# rega.net
KiCad netlist of a schematic drawn in EAGLE
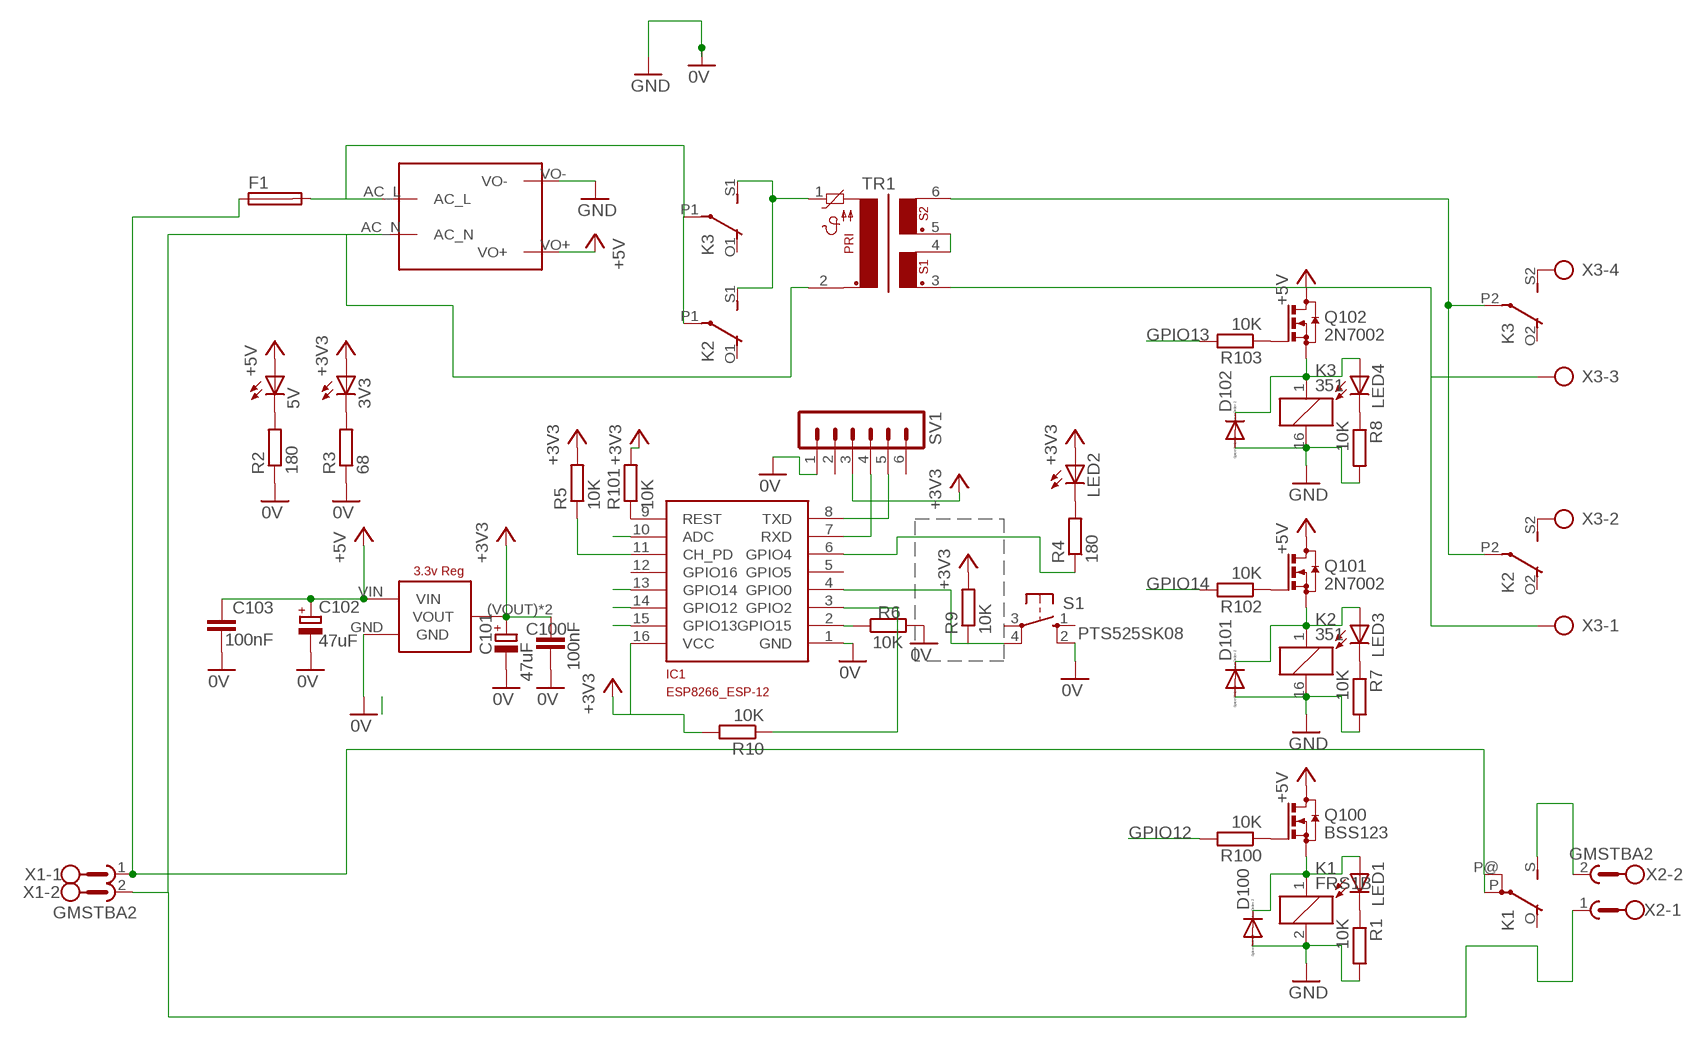
[diagram p0: schematic, sheet 1]

(export (version "E")
  (design (tool "Eeschema 10.0.6"))
  (components
    (comp (ref "3V3")
      (value "LEDCHIPLED_0805")
      (footprint "eagle-import:CHIPLED_0805")
      (libsource (lib "eagle-import") (part "LEDCHIPLED_0805"))
    )
    (comp (ref "5V")
      (value "LEDCHIPLED_0805")
      (footprint "eagle-import:CHIPLED_0805")
      (libsource (lib "eagle-import") (part "LEDCHIPLED_0805"))
    )
    (comp (ref "C100")
      (value "100nF")
      (footprint "eagle-import:C0805")
      (libsource (lib "eagle-import") (part "C-EUC0805"))
    )
    (comp (ref "C101")
      (value "47uF")
      (footprint "eagle-import:CT3528")
      (libsource (lib "eagle-import") (part "CPOL-EUCT3528"))
    )
    (comp (ref "C102")
      (value "47uF")
      (footprint "eagle-import:CT3528")
      (libsource (lib "eagle-import") (part "CPOL-EUCT3528"))
    )
    (comp (ref "C103")
      (value "100nF")
      (footprint "eagle-import:C0805")
      (libsource (lib "eagle-import") (part "C-EUC0805"))
    )
    (comp (ref "D100")
      (value "DIODE-SOD80C")
      (footprint "eagle-import:SOD80C")
      (libsource (lib "eagle-import") (part "DIODE-SOD80C"))
    )
    (comp (ref "D101")
      (value "DIODE-SOD80C")
      (footprint "eagle-import:SOD80C")
      (libsource (lib "eagle-import") (part "DIODE-SOD80C"))
    )
    (comp (ref "D102")
      (value "DIODE-SOD80C")
      (footprint "eagle-import:SOD80C")
      (libsource (lib "eagle-import") (part "DIODE-SOD80C"))
    )
    (comp (ref "F1")
      (value "LITTLEFUSESMD")
      (footprint "eagle-import:SMD")
      (libsource (lib "eagle-import") (part "LITTLEFUSESMD"))
    )
    (comp (ref "IC1")
      (value "ESP8266_ESP-12")
      (footprint "eagle-import:ESP8266-ESP12")
      (libsource (lib "eagle-import") (part "ESP8266_ESP-12"))
    )
    (comp (ref "K1")
      (value "FRS1B")
      (footprint "eagle-import:FRS1B")
      (libsource (lib "eagle-import") (part "FRS1B"))
    )
    (comp (ref "K2")
      (value "351")
      (footprint "eagle-import:351")
      (libsource (lib "eagle-import") (part "351"))
    )
    (comp (ref "K3")
      (value "351")
      (footprint "eagle-import:351")
      (libsource (lib "eagle-import") (part "351"))
    )
    (comp (ref "LED1")
      (value "LEDSML0805")
      (footprint "eagle-import:SML0805")
      (libsource (lib "eagle-import") (part "LEDSML0805"))
    )
    (comp (ref "LED2")
      (value "LEDCHIPLED_0805")
      (footprint "eagle-import:CHIPLED_0805")
      (libsource (lib "eagle-import") (part "LEDCHIPLED_0805"))
    )
    (comp (ref "LED3")
      (value "LEDSML0805")
      (footprint "eagle-import:SML0805")
      (libsource (lib "eagle-import") (part "LEDSML0805"))
    )
    (comp (ref "LED4")
      (value "LEDSML0805")
      (footprint "eagle-import:SML0805")
      (libsource (lib "eagle-import") (part "LEDSML0805"))
    )
    (comp (ref "Q100")
      (value "BSS123")
      (footprint "eagle-import:SOT23")
      (libsource (lib "eagle-import") (part "BSS123"))
    )
    (comp (ref "Q101")
      (value "2N7002")
      (footprint "eagle-import:SOT23")
      (libsource (lib "eagle-import") (part "BSS123"))
    )
    (comp (ref "Q102")
      (value "2N7002")
      (footprint "eagle-import:SOT23")
      (libsource (lib "eagle-import") (part "BSS123"))
    )
    (comp (ref "R1")
      (value "10K")
      (footprint "eagle-import:R0805")
      (libsource (lib "eagle-import") (part "resistor_R-EU_R0805"))
    )
    (comp (ref "R2")
      (value "180")
      (footprint "eagle-import:R0805")
      (libsource (lib "eagle-import") (part "R-EU_R0805"))
    )
    (comp (ref "R3")
      (value "68")
      (footprint "eagle-import:R0805")
      (libsource (lib "eagle-import") (part "R-EU_R0805"))
    )
    (comp (ref "R4")
      (value "180")
      (footprint "eagle-import:R0805")
      (libsource (lib "eagle-import") (part "R-EU_R0805"))
    )
    (comp (ref "R5")
      (value "10K")
      (footprint "eagle-import:R0805")
      (libsource (lib "eagle-import") (part "R-EU_R0805"))
    )
    (comp (ref "R6")
      (value "10K")
      (footprint "eagle-import:R0805")
      (libsource (lib "eagle-import") (part "R-EU_R0805"))
    )
    (comp (ref "R7")
      (value "10K")
      (footprint "eagle-import:R0805")
      (libsource (lib "eagle-import") (part "resistor_R-EU_R0805"))
    )
    (comp (ref "R8")
      (value "10K")
      (footprint "eagle-import:R0805")
      (libsource (lib "eagle-import") (part "resistor_R-EU_R0805"))
    )
    (comp (ref "R9")
      (value "10K")
      (footprint "eagle-import:R0805")
      (libsource (lib "eagle-import") (part "R-EU_R0805"))
    )
    (comp (ref "R10")
      (value "10K")
      (footprint "eagle-import:R0805")
      (libsource (lib "eagle-import") (part "R-EU_R0805"))
    )
    (comp (ref "R100")
      (value "10K")
      (footprint "eagle-import:R0805")
      (libsource (lib "eagle-import") (part "resistor_R-EU_R0805"))
    )
    (comp (ref "R101")
      (value "10K")
      (footprint "eagle-import:R0805")
      (libsource (lib "eagle-import") (part "R-EU_R0805"))
    )
    (comp (ref "R102")
      (value "10K")
      (footprint "eagle-import:R0805")
      (libsource (lib "eagle-import") (part "resistor_R-EU_R0805"))
    )
    (comp (ref "R103")
      (value "10K")
      (footprint "eagle-import:R0805")
      (libsource (lib "eagle-import") (part "resistor_R-EU_R0805"))
    )
    (comp (ref "S1")
      (value "PTS525SK08")
      (footprint "eagle-import:SM08")
      (fields (field (name "MF") "C&K Components") (field (name "MPN") "PTS525SK08SMTR2LFS"))
      (libsource (lib "eagle-import") (part "PTS52508SK"))
    )
    (comp (ref "SV1")
      (value "MA06-1")
      (footprint "eagle-import:MA06-1")
      (libsource (lib "eagle-import") (part "MA06-1"))
    )
    (comp (ref "TR1")
      (value "PT13-2")
      (footprint "eagle-import:PT13-2")
      (libsource (lib "eagle-import") (part "PT13-2"))
    )
    (comp (ref "U$1")
      (value "MAINS_CONVERTERS")
      (footprint "eagle-import:HLK-PM01")
      (libsource (lib "eagle-import") (part "MAINS_CONVERTERS"))
    )
    (comp (ref "U$100")
      (value "LD1117")
      (footprint "eagle-import:LD1117SOT-223")
      (libsource (lib "eagle-import") (part "LD1117"))
    )
    (comp (ref "X1")
      (value "GMSTBA2")
      (footprint "eagle-import:GMSTBA2")
      (fields (field (name "MF") "FARNELL") (field (name "MPN") "1757242"))
      (libsource (lib "eagle-import") (part "GMSTBA2"))
    )
    (comp (ref "X2")
      (value "GMSTBA2")
      (footprint "eagle-import:GMSTBA2")
      (fields (field (name "MF") "FARNELL") (field (name "MPN") "1757242"))
      (libsource (lib "eagle-import") (part "GMSTBA2"))
    )
    (comp (ref "X3")
      (value "AK300/4")
      (footprint "eagle-import:AK300_4")
      (libsource (lib "eagle-import") (part "AK300/4"))
    )
  )
  (nets
    (net (code "1") (name "+3V3") (class "Default")
      (node (ref "3V3") (pin "A") (pinfunction "A_A") (pintype "passive"))
      (node (ref "C100") (pin "1") (pinfunction "1_1") (pintype "passive"))
      (node (ref "C101") (pin "+") (pinfunction "+_+") (pintype "passive"))
      (node (ref "IC1") (pin "16") (pinfunction "VCC_16") (pintype "bidirectional"))
      (node (ref "LED2") (pin "A") (pinfunction "A_A") (pintype "passive"))
      (node (ref "R10") (pin "2") (pinfunction "2_2") (pintype "passive"))
      (node (ref "R101") (pin "2") (pinfunction "2_2") (pintype "passive"))
      (node (ref "R5") (pin "2") (pinfunction "2_2") (pintype "passive"))
      (node (ref "R9") (pin "2") (pinfunction "2_2") (pintype "passive"))
      (node (ref "SV1") (pin "3") (pinfunction "3_3") (pintype "passive"))
      (node (ref "U$100") (pin "(VOUT)") (pinfunction "VOUT_(VOUT)") (pintype "bidirectional"))
      (node (ref "U$100") (pin "VOUT") (pinfunction "VOUT_VOUT") (pintype "bidirectional"))
    )
    (net (code "2") (name "+5V") (class "Default")
      (node (ref "5V") (pin "A") (pinfunction "A_A") (pintype "passive"))
      (node (ref "C102") (pin "+") (pinfunction "+_+") (pintype "passive"))
      (node (ref "C103") (pin "1") (pinfunction "1_1") (pintype "passive"))
      (node (ref "Q100") (pin "3") (pinfunction "D_3") (pintype "passive"))
      (node (ref "Q101") (pin "3") (pinfunction "D_3") (pintype "passive"))
      (node (ref "Q102") (pin "3") (pinfunction "D_3") (pintype "passive"))
      (node (ref "U$1") (pin "VO+") (pinfunction "VO+_VO+") (pintype "output"))
      (node (ref "U$100") (pin "VIN") (pinfunction "VIN_VIN") (pintype "bidirectional"))
    )
    (net (code "3") (name "/GPIO12") (class "Default")
      (node (ref "IC1") (pin "14") (pinfunction "GPIO12_14") (pintype "bidirectional"))
      (node (ref "R100") (pin "2") (pinfunction "2_2") (pintype "passive"))
    )
    (net (code "4") (name "/GPIO13") (class "Default")
      (node (ref "IC1") (pin "15") (pinfunction "GPIO13_15") (pintype "bidirectional"))
      (node (ref "R103") (pin "2") (pinfunction "2_2") (pintype "passive"))
    )
    (net (code "5") (name "/GPIO14") (class "Default")
      (node (ref "IC1") (pin "13") (pinfunction "GPIO14_13") (pintype "bidirectional"))
      (node (ref "R102") (pin "2") (pinfunction "2_2") (pintype "passive"))
    )
    (net (code "6") (name "0V") (class "Default")
      (node (ref "C100") (pin "2") (pinfunction "2_2") (pintype "passive"))
      (node (ref "C101") (pin "-") (pinfunction "-_-") (pintype "passive"))
      (node (ref "C102") (pin "-") (pinfunction "-_-") (pintype "passive"))
      (node (ref "C103") (pin "2") (pinfunction "2_2") (pintype "passive"))
      (node (ref "D100") (pin "A") (pinfunction "A_A") (pintype "passive"))
      (node (ref "D101") (pin "A") (pinfunction "A_A") (pintype "passive"))
      (node (ref "D102") (pin "A") (pinfunction "A_A") (pintype "passive"))
      (node (ref "IC1") (pin "1") (pinfunction "GND_1") (pintype "bidirectional"))
      (node (ref "K1") (pin "2") (pinfunction "2_2") (pintype "passive"))
      (node (ref "K2") (pin "16") (pinfunction "2_16") (pintype "passive"))
      (node (ref "K3") (pin "16") (pinfunction "2_16") (pintype "passive"))
      (node (ref "R1") (pin "2") (pinfunction "2_2") (pintype "passive"))
      (node (ref "R2") (pin "1") (pinfunction "1_1") (pintype "passive"))
      (node (ref "R3") (pin "1") (pinfunction "1_1") (pintype "passive"))
      (node (ref "R6") (pin "2") (pinfunction "2_2") (pintype "passive"))
      (node (ref "R7") (pin "2") (pinfunction "2_2") (pintype "passive"))
      (node (ref "R8") (pin "2") (pinfunction "2_2") (pintype "passive"))
      (node (ref "S1") (pin "2") (pinfunction "S_2") (pintype "passive"))
      (node (ref "SV1") (pin "1") (pinfunction "1_1") (pintype "passive"))
      (node (ref "U$1") (pin "VO-") (pinfunction "VO-_VO-") (pintype "output"))
      (node (ref "U$100") (pin "GND") (pinfunction "GND_GND") (pintype "bidirectional"))
    )
    (net (code "7") (name "Net-(3V3-PadC)") (class "Default")
      (node (ref "3V3") (pin "C") (pinfunction "C_C") (pintype "passive"))
      (node (ref "R3") (pin "2") (pinfunction "2_2") (pintype "passive"))
    )
    (net (code "8") (name "Net-(5V-PadC)") (class "Default")
      (node (ref "5V") (pin "C") (pinfunction "C_C") (pintype "passive"))
      (node (ref "R2") (pin "2") (pinfunction "2_2") (pintype "passive"))
    )
    (net (code "9") (name "Net-(F1-1)") (class "Default")
      (node (ref "F1") (pin "P$1") (pinfunction "1_P$1") (pintype "passive"))
      (node (ref "K1") (pin "P") (pinfunction "P_P") (pintype "passive"))
      (node (ref "K1") (pin "P@") (pinfunction "P_P@") (pintype "passive"))
      (node (ref "X1") (pin "1") (pinfunction "1_1") (pintype "passive"))
    )
    (net (code "10") (name "Net-(F1-2)") (class "Default")
      (node (ref "F1") (pin "P$2") (pinfunction "2_P$2") (pintype "passive"))
      (node (ref "K2") (pin "P1") (pinfunction "P_P1") (pintype "passive"))
      (node (ref "K3") (pin "P1") (pinfunction "P_P1") (pintype "passive"))
      (node (ref "U$1") (pin "AC_L") (pinfunction "AC_L_AC_L") (pintype "input"))
    )
    (net (code "11") (name "Net-(IC1-CH_PD)") (class "Default")
      (node (ref "IC1") (pin "11") (pinfunction "CH_PD_11") (pintype "bidirectional"))
      (node (ref "R5") (pin "1") (pinfunction "1_1") (pintype "passive"))
    )
    (net (code "12") (name "Net-(IC1-GPIO0)") (class "Default")
      (node (ref "IC1") (pin "4") (pinfunction "GPIO0_4") (pintype "bidirectional"))
      (node (ref "R9") (pin "1") (pinfunction "1_1") (pintype "passive"))
      (node (ref "S1") (pin "4") (pinfunction "P_4") (pintype "passive"))
    )
    (net (code "13") (name "Net-(IC1-GPIO2)") (class "Default")
      (node (ref "IC1") (pin "3") (pinfunction "GPIO2_3") (pintype "bidirectional"))
      (node (ref "R10") (pin "1") (pinfunction "1_1") (pintype "passive"))
    )
    (net (code "14") (name "Net-(IC1-GPIO4)") (class "Default")
      (node (ref "IC1") (pin "6") (pinfunction "GPIO4_6") (pintype "bidirectional"))
      (node (ref "R4") (pin "1") (pinfunction "1_1") (pintype "passive"))
    )
    (net (code "15") (name "Net-(IC1-GPIO15)") (class "Default")
      (node (ref "IC1") (pin "2") (pinfunction "GPIO15_2") (pintype "bidirectional"))
      (node (ref "R6") (pin "1") (pinfunction "1_1") (pintype "passive"))
    )
    (net (code "16") (name "Net-(IC1-REST)") (class "Default")
      (node (ref "IC1") (pin "9") (pinfunction "REST_9") (pintype "bidirectional"))
      (node (ref "R101") (pin "1") (pinfunction "1_1") (pintype "passive"))
    )
    (net (code "17") (name "Net-(IC1-RXD)") (class "Default")
      (node (ref "IC1") (pin "7") (pinfunction "RXD_7") (pintype "bidirectional"))
      (node (ref "SV1") (pin "4") (pinfunction "4_4") (pintype "passive"))
    )
    (net (code "18") (name "Net-(IC1-TXD)") (class "Default")
      (node (ref "IC1") (pin "8") (pinfunction "TXD_8") (pintype "bidirectional"))
      (node (ref "SV1") (pin "5") (pinfunction "5_5") (pintype "passive"))
    )
    (net (code "19") (name "Net-(K2B-S)") (class "Default")
      (node (ref "K2") (pin "S1") (pinfunction "S_S1") (pintype "passive"))
      (node (ref "K3") (pin "S1") (pinfunction "S_S1") (pintype "passive"))
      (node (ref "TR1") (pin "1") (pinfunction "1_1") (pintype "passive"))
    )
    (net (code "20") (name "Net-(K2C-P)") (class "Default")
      (node (ref "K2") (pin "P2") (pinfunction "P_P2") (pintype "passive"))
      (node (ref "K3") (pin "P2") (pinfunction "P_P2") (pintype "passive"))
      (node (ref "TR1") (pin "6") (pinfunction "6_6") (pintype "passive"))
    )
    (net (code "21") (name "Net-(K2C-S)") (class "Default")
      (node (ref "K2") (pin "S2") (pinfunction "S_S2") (pintype "passive"))
      (node (ref "X3") (pin "2") (pinfunction "KL_2") (pintype "passive"))
    )
    (net (code "22") (name "Net-(K3C-S)") (class "Default")
      (node (ref "K3") (pin "S2") (pinfunction "S_S2") (pintype "passive"))
      (node (ref "X3") (pin "4") (pinfunction "KL_4") (pintype "passive"))
    )
    (net (code "23") (name "Net-(LED1-PadC)") (class "Default")
      (node (ref "LED1") (pin "C") (pinfunction "C_C") (pintype "passive"))
      (node (ref "R1") (pin "1") (pinfunction "1_1") (pintype "passive"))
    )
    (net (code "24") (name "Net-(LED2-PadC)") (class "Default")
      (node (ref "LED2") (pin "C") (pinfunction "C_C") (pintype "passive"))
      (node (ref "R4") (pin "2") (pinfunction "2_2") (pintype "passive"))
    )
    (net (code "25") (name "Net-(LED3-PadC)") (class "Default")
      (node (ref "LED3") (pin "C") (pinfunction "C_C") (pintype "passive"))
      (node (ref "R7") (pin "1") (pinfunction "1_1") (pintype "passive"))
    )
    (net (code "26") (name "Net-(LED4-PadC)") (class "Default")
      (node (ref "LED4") (pin "C") (pinfunction "C_C") (pintype "passive"))
      (node (ref "R8") (pin "1") (pinfunction "1_1") (pintype "passive"))
    )
    (net (code "27") (name "Net-(Q100-G)") (class "Default")
      (node (ref "Q100") (pin "1") (pinfunction "G_1") (pintype "passive"))
      (node (ref "R100") (pin "1") (pinfunction "1_1") (pintype "passive"))
    )
    (net (code "28") (name "Net-(Q100-S)") (class "Default")
      (node (ref "D100") (pin "C") (pinfunction "C_C") (pintype "passive"))
      (node (ref "K1") (pin "1") (pinfunction "1_1") (pintype "passive"))
      (node (ref "LED1") (pin "A") (pinfunction "A_A") (pintype "passive"))
      (node (ref "Q100") (pin "2") (pinfunction "S_2") (pintype "passive"))
    )
    (net (code "29") (name "Net-(Q101-G)") (class "Default")
      (node (ref "Q101") (pin "1") (pinfunction "G_1") (pintype "passive"))
      (node (ref "R102") (pin "1") (pinfunction "1_1") (pintype "passive"))
    )
    (net (code "30") (name "Net-(Q101-S)") (class "Default")
      (node (ref "D101") (pin "C") (pinfunction "C_C") (pintype "passive"))
      (node (ref "K2") (pin "1") (pinfunction "1_1") (pintype "passive"))
      (node (ref "LED3") (pin "A") (pinfunction "A_A") (pintype "passive"))
      (node (ref "Q101") (pin "2") (pinfunction "S_2") (pintype "passive"))
    )
    (net (code "31") (name "Net-(Q102-G)") (class "Default")
      (node (ref "Q102") (pin "1") (pinfunction "G_1") (pintype "passive"))
      (node (ref "R103") (pin "1") (pinfunction "1_1") (pintype "passive"))
    )
    (net (code "32") (name "Net-(Q102-S)") (class "Default")
      (node (ref "D102") (pin "C") (pinfunction "C_C") (pintype "passive"))
      (node (ref "K3") (pin "1") (pinfunction "1_1") (pintype "passive"))
      (node (ref "LED4") (pin "A") (pinfunction "A_A") (pintype "passive"))
      (node (ref "Q102") (pin "2") (pinfunction "S_2") (pintype "passive"))
    )
    (net (code "33") (name "Net-(TR1-Pad4)") (class "Default")
      (node (ref "TR1") (pin "4") (pinfunction "4_4") (pintype "passive"))
      (node (ref "TR1") (pin "5") (pinfunction "5_5") (pintype "passive"))
    )
    (net (code "34") (name "Net-(X1B-1)") (class "Default")
      (node (ref "TR1") (pin "2") (pinfunction "2_2") (pintype "passive"))
      (node (ref "U$1") (pin "AC_N") (pinfunction "AC_N_AC_N") (pintype "input"))
      (node (ref "X1") (pin "2") (pinfunction "1_2") (pintype "passive"))
      (node (ref "X2") (pin "1") (pinfunction "1_1") (pintype "passive"))
    )
    (net (code "35") (name "Net-(X2B-1)") (class "Default")
      (node (ref "K1") (pin "S") (pinfunction "S_S") (pintype "passive"))
      (node (ref "X2") (pin "2") (pinfunction "1_2") (pintype "passive"))
    )
    (net (code "36") (name "Net-(X3A-KL)") (class "Default")
      (node (ref "TR1") (pin "3") (pinfunction "3_3") (pintype "passive"))
      (node (ref "X3") (pin "1") (pinfunction "KL_1") (pintype "passive"))
      (node (ref "X3") (pin "3") (pinfunction "KL_3") (pintype "passive"))
    )
    (net (code "37") (name "unconnected-(IC1-ADC-Pad10)") (class "Default")
      (node (ref "IC1") (pin "10") (pinfunction "ADC_10") (pintype "bidirectional"))
    )
    (net (code "38") (name "unconnected-(IC1-GPIO5-Pad5)") (class "Default")
      (node (ref "IC1") (pin "5") (pinfunction "GPIO5_5") (pintype "bidirectional"))
    )
    (net (code "39") (name "unconnected-(IC1-GPIO16-Pad12)") (class "Default")
      (node (ref "IC1") (pin "12") (pinfunction "GPIO16_12") (pintype "bidirectional"))
    )
    (net (code "40") (name "unconnected-(K1-PadO)") (class "Default")
      (node (ref "K1") (pin "O") (pinfunction "O_O") (pintype "passive"))
    )
    (net (code "41") (name "unconnected-(K2B-O-PadO1)") (class "Default")
      (node (ref "K2") (pin "O1") (pinfunction "O_O1") (pintype "passive"))
    )
    (net (code "42") (name "unconnected-(K2C-O-PadO2)") (class "Default")
      (node (ref "K2") (pin "O2") (pinfunction "O_O2") (pintype "passive"))
    )
    (net (code "43") (name "unconnected-(K3B-O-PadO1)") (class "Default")
      (node (ref "K3") (pin "O1") (pinfunction "O_O1") (pintype "passive"))
    )
    (net (code "44") (name "unconnected-(K3C-O-PadO2)") (class "Default")
      (node (ref "K3") (pin "O2") (pinfunction "O_O2") (pintype "passive"))
    )
    (net (code "45") (name "unconnected-(S1-P-Pad3)") (class "Default")
      (node (ref "S1") (pin "3") (pinfunction "P_3") (pintype "passive"))
    )
    (net (code "46") (name "unconnected-(S1-S-Pad1)") (class "Default")
      (node (ref "S1") (pin "1") (pinfunction "S_1") (pintype "passive"))
    )
    (net (code "47") (name "unconnected-(SV1-Pad2)") (class "Default")
      (node (ref "SV1") (pin "2") (pinfunction "2_2") (pintype "passive"))
    )
    (net (code "48") (name "unconnected-(SV1-Pad6)") (class "Default")
      (node (ref "SV1") (pin "6") (pinfunction "6_6") (pintype "passive"))
    )
  )
)
